# solenoidcontroller.net
KiCad netlist of a schematic drawn in EAGLE
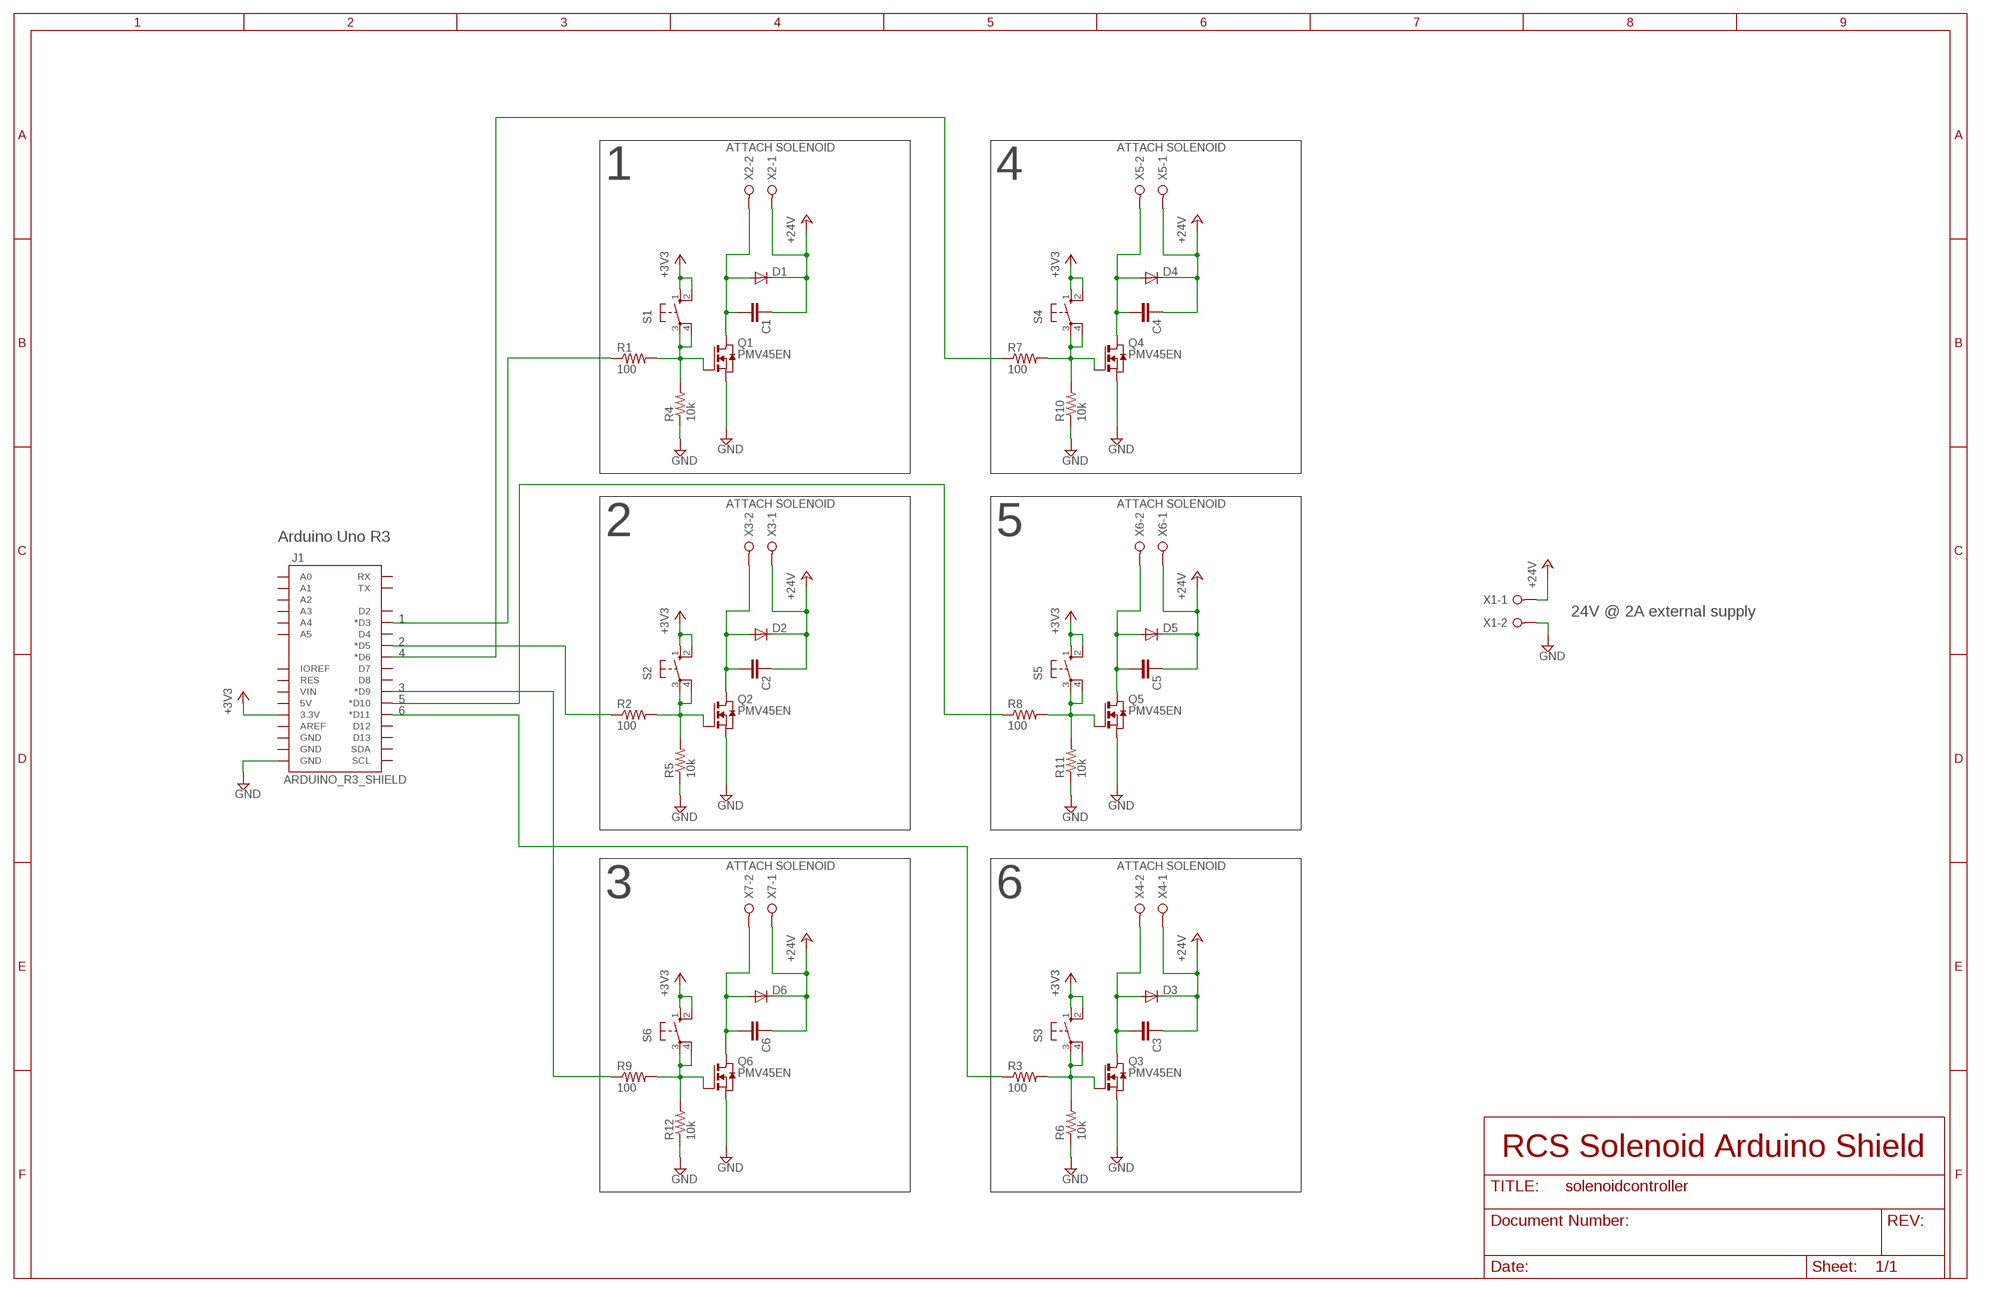
[diagram p0: schematic, sheet 1]

(export (version "E")
  (design (tool "Eeschema 10.0.6"))
  (components
    (comp (ref "C1")
      (value "C-EUC0603")
      (footprint "eagle-import:C0603")
      (libsource (lib "eagle-import") (part "C-EUC0603"))
    )
    (comp (ref "C2")
      (value "C-EUC0603")
      (footprint "eagle-import:C0603")
      (libsource (lib "eagle-import") (part "C-EUC0603"))
    )
    (comp (ref "C3")
      (value "C-EUC0603")
      (footprint "eagle-import:C0603")
      (libsource (lib "eagle-import") (part "C-EUC0603"))
    )
    (comp (ref "C4")
      (value "C-EUC0603")
      (footprint "eagle-import:C0603")
      (libsource (lib "eagle-import") (part "C-EUC0603"))
    )
    (comp (ref "C5")
      (value "C-EUC0603")
      (footprint "eagle-import:C0603")
      (libsource (lib "eagle-import") (part "C-EUC0603"))
    )
    (comp (ref "C6")
      (value "C-EUC0603")
      (footprint "eagle-import:C0603")
      (libsource (lib "eagle-import") (part "C-EUC0603"))
    )
    (comp (ref "D1")
      (value "DIODE-DO214BA")
      (footprint "eagle-import:DO214BA")
      (libsource (lib "eagle-import") (part "DIODE-DO214BA"))
    )
    (comp (ref "D2")
      (value "DIODE-DO214BA")
      (footprint "eagle-import:DO214BA")
      (libsource (lib "eagle-import") (part "DIODE-DO214BA"))
    )
    (comp (ref "D3")
      (value "DIODE-DO214BA")
      (footprint "eagle-import:DO214BA")
      (libsource (lib "eagle-import") (part "DIODE-DO214BA"))
    )
    (comp (ref "D4")
      (value "DIODE-DO214BA")
      (footprint "eagle-import:DO214BA")
      (libsource (lib "eagle-import") (part "DIODE-DO214BA"))
    )
    (comp (ref "D5")
      (value "DIODE-DO214BA")
      (footprint "eagle-import:DO214BA")
      (libsource (lib "eagle-import") (part "DIODE-DO214BA"))
    )
    (comp (ref "D6")
      (value "DIODE-DO214BA")
      (footprint "eagle-import:DO214BA")
      (libsource (lib "eagle-import") (part "DIODE-DO214BA"))
    )
    (comp (ref "J1")
      (value "ARDUINO_R3_SHIELD")
      (footprint "eagle-import:UNO_R3_SHIELD")
      (libsource (lib "eagle-import") (part "ARDUINO_R3_SHIELD"))
    )
    (comp (ref "Q1")
      (value "PMV45EN")
      (footprint "eagle-import:SOT23")
      (libsource (lib "eagle-import") (part "PMV45EN"))
    )
    (comp (ref "Q2")
      (value "PMV45EN")
      (footprint "eagle-import:SOT23")
      (libsource (lib "eagle-import") (part "PMV45EN"))
    )
    (comp (ref "Q3")
      (value "PMV45EN")
      (footprint "eagle-import:SOT23")
      (libsource (lib "eagle-import") (part "PMV45EN"))
    )
    (comp (ref "Q4")
      (value "PMV45EN")
      (footprint "eagle-import:SOT23")
      (libsource (lib "eagle-import") (part "PMV45EN"))
    )
    (comp (ref "Q5")
      (value "PMV45EN")
      (footprint "eagle-import:SOT23")
      (libsource (lib "eagle-import") (part "PMV45EN"))
    )
    (comp (ref "Q6")
      (value "PMV45EN")
      (footprint "eagle-import:SOT23")
      (libsource (lib "eagle-import") (part "PMV45EN"))
    )
    (comp (ref "R1")
      (value "100")
      (footprint "eagle-import:R0603")
      (libsource (lib "eagle-import") (part "R-US_R0603"))
    )
    (comp (ref "R2")
      (value "100")
      (footprint "eagle-import:R0603")
      (libsource (lib "eagle-import") (part "R-US_R0603"))
    )
    (comp (ref "R3")
      (value "100")
      (footprint "eagle-import:R0603")
      (libsource (lib "eagle-import") (part "R-US_R0603"))
    )
    (comp (ref "R4")
      (value "10k")
      (footprint "eagle-import:R0603")
      (libsource (lib "eagle-import") (part "R-US_R0603"))
    )
    (comp (ref "R5")
      (value "10k")
      (footprint "eagle-import:R0603")
      (libsource (lib "eagle-import") (part "R-US_R0603"))
    )
    (comp (ref "R6")
      (value "10k")
      (footprint "eagle-import:R0603")
      (libsource (lib "eagle-import") (part "R-US_R0603"))
    )
    (comp (ref "R7")
      (value "100")
      (footprint "eagle-import:R0603")
      (libsource (lib "eagle-import") (part "R-US_R0603"))
    )
    (comp (ref "R8")
      (value "100")
      (footprint "eagle-import:R0603")
      (libsource (lib "eagle-import") (part "R-US_R0603"))
    )
    (comp (ref "R9")
      (value "100")
      (footprint "eagle-import:R0603")
      (libsource (lib "eagle-import") (part "R-US_R0603"))
    )
    (comp (ref "R10")
      (value "10k")
      (footprint "eagle-import:R0603")
      (libsource (lib "eagle-import") (part "R-US_R0603"))
    )
    (comp (ref "R11")
      (value "10k")
      (footprint "eagle-import:R0603")
      (libsource (lib "eagle-import") (part "R-US_R0603"))
    )
    (comp (ref "R12")
      (value "10k")
      (footprint "eagle-import:R0603")
      (libsource (lib "eagle-import") (part "R-US_R0603"))
    )
    (comp (ref "S1")
      (value "10-XX")
      (footprint "eagle-import:B3F-10XX")
      (fields (field (name "MPN") "B3F-1000"))
      (libsource (lib "eagle-import") (part "10-XX"))
    )
    (comp (ref "S2")
      (value "10-XX")
      (footprint "eagle-import:B3F-10XX")
      (fields (field (name "MPN") "B3F-1000"))
      (libsource (lib "eagle-import") (part "10-XX"))
    )
    (comp (ref "S3")
      (value "10-XX")
      (footprint "eagle-import:B3F-10XX")
      (fields (field (name "MPN") "B3F-1000"))
      (libsource (lib "eagle-import") (part "10-XX"))
    )
    (comp (ref "S4")
      (value "10-XX")
      (footprint "eagle-import:B3F-10XX")
      (fields (field (name "MPN") "B3F-1000"))
      (libsource (lib "eagle-import") (part "10-XX"))
    )
    (comp (ref "S5")
      (value "10-XX")
      (footprint "eagle-import:B3F-10XX")
      (fields (field (name "MPN") "B3F-1000"))
      (libsource (lib "eagle-import") (part "10-XX"))
    )
    (comp (ref "S6")
      (value "10-XX")
      (footprint "eagle-import:B3F-10XX")
      (fields (field (name "MPN") "B3F-1000"))
      (libsource (lib "eagle-import") (part "10-XX"))
    )
    (comp (ref "X1")
      (value "W237-02P")
      (footprint "eagle-import:W237-132")
      (libsource (lib "eagle-import") (part "W237-02P"))
    )
    (comp (ref "X2")
      (value "W237-02P")
      (footprint "eagle-import:W237-132")
      (libsource (lib "eagle-import") (part "W237-02P"))
    )
    (comp (ref "X3")
      (value "W237-02P")
      (footprint "eagle-import:W237-132")
      (libsource (lib "eagle-import") (part "W237-02P"))
    )
    (comp (ref "X4")
      (value "W237-02P")
      (footprint "eagle-import:W237-132")
      (libsource (lib "eagle-import") (part "W237-02P"))
    )
    (comp (ref "X5")
      (value "W237-02P")
      (footprint "eagle-import:W237-132")
      (libsource (lib "eagle-import") (part "W237-02P"))
    )
    (comp (ref "X6")
      (value "W237-02P")
      (footprint "eagle-import:W237-132")
      (libsource (lib "eagle-import") (part "W237-02P"))
    )
    (comp (ref "X7")
      (value "W237-02P")
      (footprint "eagle-import:W237-132")
      (libsource (lib "eagle-import") (part "W237-02P"))
    )
  )
  (nets
    (net (code "1") (name "+3V3") (class "Default")
      (node (ref "J1") (pin "3.3V") (pinfunction "3.3V_3.3V") (pintype "bidirectional"))
      (node (ref "S1") (pin "1") (pinfunction "S_1") (pintype "passive"))
      (node (ref "S1") (pin "2") (pinfunction "S1_2") (pintype "passive"))
      (node (ref "S2") (pin "1") (pinfunction "S_1") (pintype "passive"))
      (node (ref "S2") (pin "2") (pinfunction "S1_2") (pintype "passive"))
      (node (ref "S3") (pin "1") (pinfunction "S_1") (pintype "passive"))
      (node (ref "S3") (pin "2") (pinfunction "S1_2") (pintype "passive"))
      (node (ref "S4") (pin "1") (pinfunction "S_1") (pintype "passive"))
      (node (ref "S4") (pin "2") (pinfunction "S1_2") (pintype "passive"))
      (node (ref "S5") (pin "1") (pinfunction "S_1") (pintype "passive"))
      (node (ref "S5") (pin "2") (pinfunction "S1_2") (pintype "passive"))
      (node (ref "S6") (pin "1") (pinfunction "S_1") (pintype "passive"))
      (node (ref "S6") (pin "2") (pinfunction "S1_2") (pintype "passive"))
    )
    (net (code "2") (name "+24V") (class "Default")
      (node (ref "C1") (pin "1") (pinfunction "1_1") (pintype "passive"))
      (node (ref "C2") (pin "1") (pinfunction "1_1") (pintype "passive"))
      (node (ref "C3") (pin "1") (pinfunction "1_1") (pintype "passive"))
      (node (ref "C4") (pin "1") (pinfunction "1_1") (pintype "passive"))
      (node (ref "C5") (pin "1") (pinfunction "1_1") (pintype "passive"))
      (node (ref "C6") (pin "1") (pinfunction "1_1") (pintype "passive"))
      (node (ref "D1") (pin "C") (pinfunction "C_C") (pintype "passive"))
      (node (ref "D2") (pin "C") (pinfunction "C_C") (pintype "passive"))
      (node (ref "D3") (pin "C") (pinfunction "C_C") (pintype "passive"))
      (node (ref "D4") (pin "C") (pinfunction "C_C") (pintype "passive"))
      (node (ref "D5") (pin "C") (pinfunction "C_C") (pintype "passive"))
      (node (ref "D6") (pin "C") (pinfunction "C_C") (pintype "passive"))
      (node (ref "X1") (pin "1") (pinfunction "KL_1") (pintype "passive"))
      (node (ref "X2") (pin "1") (pinfunction "KL_1") (pintype "passive"))
      (node (ref "X3") (pin "1") (pinfunction "KL_1") (pintype "passive"))
      (node (ref "X4") (pin "1") (pinfunction "KL_1") (pintype "passive"))
      (node (ref "X5") (pin "1") (pinfunction "KL_1") (pintype "passive"))
      (node (ref "X6") (pin "1") (pinfunction "KL_1") (pintype "passive"))
      (node (ref "X7") (pin "1") (pinfunction "KL_1") (pintype "passive"))
    )
    (net (code "3") (name "/1") (class "Default")
      (node (ref "J1") (pin "D3") (pinfunction "*D3_D3") (pintype "bidirectional"))
      (node (ref "R1") (pin "1") (pinfunction "1_1") (pintype "passive"))
    )
    (net (code "4") (name "/2") (class "Default")
      (node (ref "J1") (pin "D5") (pinfunction "*D5_D5") (pintype "bidirectional"))
      (node (ref "R2") (pin "1") (pinfunction "1_1") (pintype "passive"))
    )
    (net (code "5") (name "/3") (class "Default")
      (node (ref "J1") (pin "D9") (pinfunction "*D9_D9") (pintype "bidirectional"))
      (node (ref "R9") (pin "1") (pinfunction "1_1") (pintype "passive"))
    )
    (net (code "6") (name "/4") (class "Default")
      (node (ref "J1") (pin "D6") (pinfunction "*D6_D6") (pintype "bidirectional"))
      (node (ref "R7") (pin "1") (pinfunction "1_1") (pintype "passive"))
    )
    (net (code "7") (name "/5") (class "Default")
      (node (ref "J1") (pin "D10") (pinfunction "*D10_D10") (pintype "bidirectional"))
      (node (ref "R8") (pin "1") (pinfunction "1_1") (pintype "passive"))
    )
    (net (code "8") (name "/6") (class "Default")
      (node (ref "J1") (pin "D11") (pinfunction "*D11_D11") (pintype "bidirectional"))
      (node (ref "R3") (pin "1") (pinfunction "1_1") (pintype "passive"))
    )
    (net (code "9") (name "GND") (class "Default")
      (node (ref "J1") (pin "GND@0") (pinfunction "GND_GND@0") (pintype "bidirectional"))
      (node (ref "Q1") (pin "2") (pinfunction "S_2") (pintype "passive"))
      (node (ref "Q2") (pin "2") (pinfunction "S_2") (pintype "passive"))
      (node (ref "Q3") (pin "2") (pinfunction "S_2") (pintype "passive"))
      (node (ref "Q4") (pin "2") (pinfunction "S_2") (pintype "passive"))
      (node (ref "Q5") (pin "2") (pinfunction "S_2") (pintype "passive"))
      (node (ref "Q6") (pin "2") (pinfunction "S_2") (pintype "passive"))
      (node (ref "R10") (pin "1") (pinfunction "1_1") (pintype "passive"))
      (node (ref "R11") (pin "1") (pinfunction "1_1") (pintype "passive"))
      (node (ref "R12") (pin "1") (pinfunction "1_1") (pintype "passive"))
      (node (ref "R4") (pin "1") (pinfunction "1_1") (pintype "passive"))
      (node (ref "R5") (pin "1") (pinfunction "1_1") (pintype "passive"))
      (node (ref "R6") (pin "1") (pinfunction "1_1") (pintype "passive"))
      (node (ref "X1") (pin "2") (pinfunction "KL_2") (pintype "passive"))
    )
    (net (code "10") (name "Net-(Q1-D)") (class "Default")
      (node (ref "C1") (pin "2") (pinfunction "2_2") (pintype "passive"))
      (node (ref "D1") (pin "A") (pinfunction "A_A") (pintype "passive"))
      (node (ref "Q1") (pin "3") (pinfunction "D_3") (pintype "passive"))
      (node (ref "X2") (pin "2") (pinfunction "KL_2") (pintype "passive"))
    )
    (net (code "11") (name "Net-(Q1-G)") (class "Default")
      (node (ref "Q1") (pin "1") (pinfunction "G_1") (pintype "passive"))
      (node (ref "R1") (pin "2") (pinfunction "2_2") (pintype "passive"))
      (node (ref "R4") (pin "2") (pinfunction "2_2") (pintype "passive"))
      (node (ref "S1") (pin "3") (pinfunction "P_3") (pintype "passive"))
      (node (ref "S1") (pin "4") (pinfunction "P1_4") (pintype "passive"))
    )
    (net (code "12") (name "Net-(Q2-D)") (class "Default")
      (node (ref "C2") (pin "2") (pinfunction "2_2") (pintype "passive"))
      (node (ref "D2") (pin "A") (pinfunction "A_A") (pintype "passive"))
      (node (ref "Q2") (pin "3") (pinfunction "D_3") (pintype "passive"))
      (node (ref "X3") (pin "2") (pinfunction "KL_2") (pintype "passive"))
    )
    (net (code "13") (name "Net-(Q2-G)") (class "Default")
      (node (ref "Q2") (pin "1") (pinfunction "G_1") (pintype "passive"))
      (node (ref "R2") (pin "2") (pinfunction "2_2") (pintype "passive"))
      (node (ref "R5") (pin "2") (pinfunction "2_2") (pintype "passive"))
      (node (ref "S2") (pin "3") (pinfunction "P_3") (pintype "passive"))
      (node (ref "S2") (pin "4") (pinfunction "P1_4") (pintype "passive"))
    )
    (net (code "14") (name "Net-(Q3-D)") (class "Default")
      (node (ref "C3") (pin "2") (pinfunction "2_2") (pintype "passive"))
      (node (ref "D3") (pin "A") (pinfunction "A_A") (pintype "passive"))
      (node (ref "Q3") (pin "3") (pinfunction "D_3") (pintype "passive"))
      (node (ref "X4") (pin "2") (pinfunction "KL_2") (pintype "passive"))
    )
    (net (code "15") (name "Net-(Q3-G)") (class "Default")
      (node (ref "Q3") (pin "1") (pinfunction "G_1") (pintype "passive"))
      (node (ref "R3") (pin "2") (pinfunction "2_2") (pintype "passive"))
      (node (ref "R6") (pin "2") (pinfunction "2_2") (pintype "passive"))
      (node (ref "S3") (pin "3") (pinfunction "P_3") (pintype "passive"))
      (node (ref "S3") (pin "4") (pinfunction "P1_4") (pintype "passive"))
    )
    (net (code "16") (name "Net-(Q4-D)") (class "Default")
      (node (ref "C4") (pin "2") (pinfunction "2_2") (pintype "passive"))
      (node (ref "D4") (pin "A") (pinfunction "A_A") (pintype "passive"))
      (node (ref "Q4") (pin "3") (pinfunction "D_3") (pintype "passive"))
      (node (ref "X5") (pin "2") (pinfunction "KL_2") (pintype "passive"))
    )
    (net (code "17") (name "Net-(Q4-G)") (class "Default")
      (node (ref "Q4") (pin "1") (pinfunction "G_1") (pintype "passive"))
      (node (ref "R10") (pin "2") (pinfunction "2_2") (pintype "passive"))
      (node (ref "R7") (pin "2") (pinfunction "2_2") (pintype "passive"))
      (node (ref "S4") (pin "3") (pinfunction "P_3") (pintype "passive"))
      (node (ref "S4") (pin "4") (pinfunction "P1_4") (pintype "passive"))
    )
    (net (code "18") (name "Net-(Q5-D)") (class "Default")
      (node (ref "C5") (pin "2") (pinfunction "2_2") (pintype "passive"))
      (node (ref "D5") (pin "A") (pinfunction "A_A") (pintype "passive"))
      (node (ref "Q5") (pin "3") (pinfunction "D_3") (pintype "passive"))
      (node (ref "X6") (pin "2") (pinfunction "KL_2") (pintype "passive"))
    )
    (net (code "19") (name "Net-(Q5-G)") (class "Default")
      (node (ref "Q5") (pin "1") (pinfunction "G_1") (pintype "passive"))
      (node (ref "R11") (pin "2") (pinfunction "2_2") (pintype "passive"))
      (node (ref "R8") (pin "2") (pinfunction "2_2") (pintype "passive"))
      (node (ref "S5") (pin "3") (pinfunction "P_3") (pintype "passive"))
      (node (ref "S5") (pin "4") (pinfunction "P1_4") (pintype "passive"))
    )
    (net (code "20") (name "Net-(Q6-D)") (class "Default")
      (node (ref "C6") (pin "2") (pinfunction "2_2") (pintype "passive"))
      (node (ref "D6") (pin "A") (pinfunction "A_A") (pintype "passive"))
      (node (ref "Q6") (pin "3") (pinfunction "D_3") (pintype "passive"))
      (node (ref "X7") (pin "2") (pinfunction "KL_2") (pintype "passive"))
    )
    (net (code "21") (name "Net-(Q6-G)") (class "Default")
      (node (ref "Q6") (pin "1") (pinfunction "G_1") (pintype "passive"))
      (node (ref "R12") (pin "2") (pinfunction "2_2") (pintype "passive"))
      (node (ref "R9") (pin "2") (pinfunction "2_2") (pintype "passive"))
      (node (ref "S6") (pin "3") (pinfunction "P_3") (pintype "passive"))
      (node (ref "S6") (pin "4") (pinfunction "P1_4") (pintype "passive"))
    )
    (net (code "22") (name "unconnected-(J1-GND-PadGND@1)") (class "Default")
      (node (ref "J1") (pin "GND@1") (pinfunction "GND_GND@1") (pintype "bidirectional"))
    )
    (net (code "23") (name "unconnected-(J1-GND-PadGND@2)") (class "Default")
      (node (ref "J1") (pin "GND@2") (pinfunction "GND_GND@2") (pintype "bidirectional"))
    )
    (net (code "24") (name "unconnected-(J1-Pad5V)") (class "Default")
      (node (ref "J1") (pin "5V") (pinfunction "5V_5V") (pintype "bidirectional"))
    )
    (net (code "25") (name "unconnected-(J1-PadA0)") (class "Default")
      (node (ref "J1") (pin "A0") (pinfunction "A0_A0") (pintype "bidirectional"))
    )
    (net (code "26") (name "unconnected-(J1-PadA1)") (class "Default")
      (node (ref "J1") (pin "A1") (pinfunction "A1_A1") (pintype "bidirectional"))
    )
    (net (code "27") (name "unconnected-(J1-PadA2)") (class "Default")
      (node (ref "J1") (pin "A2") (pinfunction "A2_A2") (pintype "bidirectional"))
    )
    (net (code "28") (name "unconnected-(J1-PadA3)") (class "Default")
      (node (ref "J1") (pin "A3") (pinfunction "A3_A3") (pintype "bidirectional"))
    )
    (net (code "29") (name "unconnected-(J1-PadA4)") (class "Default")
      (node (ref "J1") (pin "A4") (pinfunction "A4_A4") (pintype "bidirectional"))
    )
    (net (code "30") (name "unconnected-(J1-PadA5)") (class "Default")
      (node (ref "J1") (pin "A5") (pinfunction "A5_A5") (pintype "bidirectional"))
    )
    (net (code "31") (name "unconnected-(J1-PadAREF)") (class "Default")
      (node (ref "J1") (pin "AREF") (pinfunction "AREF_AREF") (pintype "bidirectional"))
    )
    (net (code "32") (name "unconnected-(J1-PadD2)") (class "Default")
      (node (ref "J1") (pin "D2") (pinfunction "D2_D2") (pintype "bidirectional"))
    )
    (net (code "33") (name "unconnected-(J1-PadD4)") (class "Default")
      (node (ref "J1") (pin "D4") (pinfunction "D4_D4") (pintype "bidirectional"))
    )
    (net (code "34") (name "unconnected-(J1-PadD7)") (class "Default")
      (node (ref "J1") (pin "D7") (pinfunction "D7_D7") (pintype "bidirectional"))
    )
    (net (code "35") (name "unconnected-(J1-PadD8)") (class "Default")
      (node (ref "J1") (pin "D8") (pinfunction "D8_D8") (pintype "bidirectional"))
    )
    (net (code "36") (name "unconnected-(J1-PadD12)") (class "Default")
      (node (ref "J1") (pin "D12") (pinfunction "D12_D12") (pintype "bidirectional"))
    )
    (net (code "37") (name "unconnected-(J1-PadD13)") (class "Default")
      (node (ref "J1") (pin "D13") (pinfunction "D13_D13") (pintype "bidirectional"))
    )
    (net (code "38") (name "unconnected-(J1-PadIOREF)") (class "Default")
      (node (ref "J1") (pin "IOREF") (pinfunction "IOREF_IOREF") (pintype "bidirectional"))
    )
    (net (code "39") (name "unconnected-(J1-PadRES)") (class "Default")
      (node (ref "J1") (pin "RES") (pinfunction "RES_RES") (pintype "bidirectional"))
    )
    (net (code "40") (name "unconnected-(J1-PadRX)") (class "Default")
      (node (ref "J1") (pin "RX") (pinfunction "RX_RX") (pintype "bidirectional"))
    )
    (net (code "41") (name "unconnected-(J1-PadSCL)") (class "Default")
      (node (ref "J1") (pin "SCL") (pinfunction "SCL_SCL") (pintype "bidirectional"))
    )
    (net (code "42") (name "unconnected-(J1-PadSDA)") (class "Default")
      (node (ref "J1") (pin "SDA") (pinfunction "SDA_SDA") (pintype "bidirectional"))
    )
    (net (code "43") (name "unconnected-(J1-PadTX)") (class "Default")
      (node (ref "J1") (pin "TX") (pinfunction "TX_TX") (pintype "bidirectional"))
    )
    (net (code "44") (name "unconnected-(J1-PadVIN)") (class "Default")
      (node (ref "J1") (pin "VIN") (pinfunction "VIN_VIN") (pintype "bidirectional"))
    )
  )
)
